# Lab10_Starter.net
KiCad netlist of a schematic drawn in EAGLE
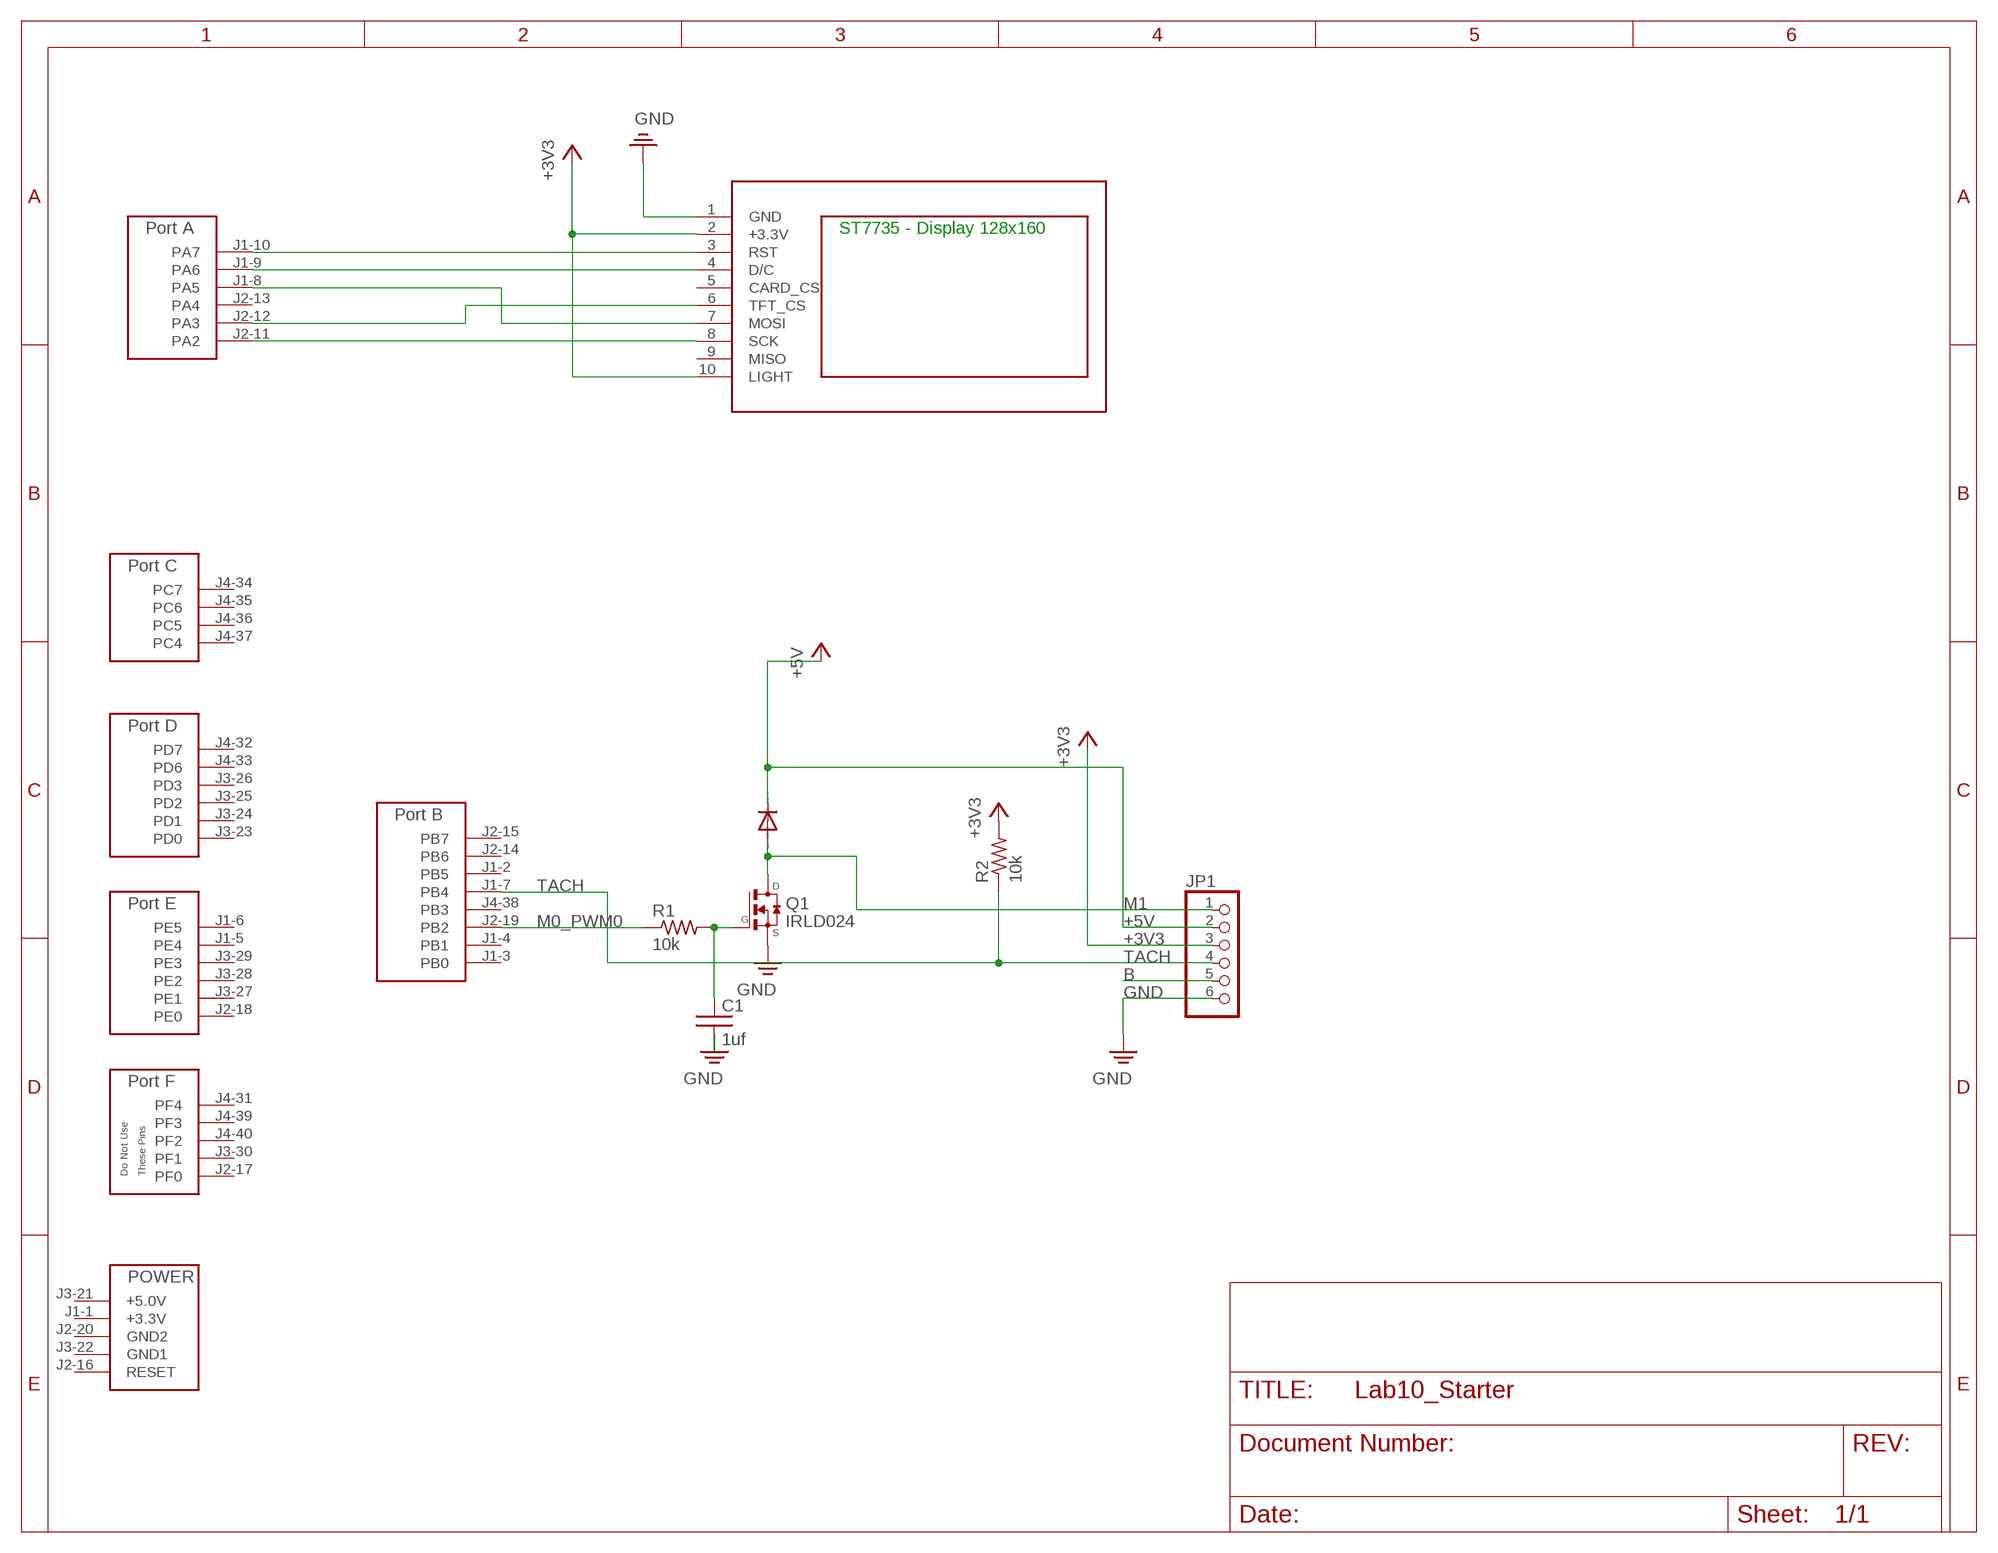
[diagram p0: schematic, sheet 1]

(export (version "E")
  (design (tool "Eeschema 10.0.6"))
  (components
    (comp (ref "C1")
      (value "1uf")
      (footprint "eagle-import:CAP200MIL")
      (libsource (lib "eagle-import") (part "CAPACITOR050-024X044"))
    )
    (comp (ref "D1")
      (value "1N914DO35-7")
      (footprint "eagle-import:DO35-7")
      (libsource (lib "eagle-import") (part "1N914DO35-7"))
    )
    (comp (ref "JP1")
      (value "PINHD-1X6")
      (footprint "eagle-import:1X06")
      (libsource (lib "eagle-import") (part "PINHD-1X6"))
    )
    (comp (ref "Q1")
      (value "IRLD024")
      (footprint "eagle-import:IRLD024")
      (libsource (lib "eagle-import") (part "IRLD024"))
    )
    (comp (ref "R1")
      (value "10k")
      (footprint "eagle-import:RES200MIL")
      (libsource (lib "eagle-import") (part "RESISTOR0204/5"))
    )
    (comp (ref "R2")
      (value "10k")
      (footprint "eagle-import:RES200MIL")
      (libsource (lib "eagle-import") (part "RESISTOR0204/5"))
    )
    (comp (ref "U$1")
      (value "TM4C_BP")
      (footprint "eagle-import:TM4C_BOOSTER_PACK")
      (libsource (lib "eagle-import") (part "TM4C_BP"))
    )
    (comp (ref "U$2")
      (value "ST7735")
      (footprint "eagle-import:ST7735")
      (libsource (lib "eagle-import") (part "ST7735"))
    )
    (comp (ref "U$3")
      (value "TM4C_BP")
      (footprint "eagle-import:TM4C_BOOSTER_PACK")
      (libsource (lib "eagle-import") (part "TM4C_BP"))
    )
  )
  (nets
    (net (code "1") (name "+3V3") (class "Default")
      (node (ref "JP1") (pin "3") (pinfunction "3_3") (pintype "passive"))
      (node (ref "R2") (pin "2") (pinfunction "2_2") (pintype "passive"))
      (node (ref "U$2") (pin "10") (pinfunction "LIGHT_10") (pintype "bidirectional"))
      (node (ref "U$2") (pin "2") (pinfunction "+3.3V_2") (pintype "bidirectional"))
    )
    (net (code "2") (name "+5V") (class "Default")
      (node (ref "D1") (pin "C") (pinfunction "C_C") (pintype "passive"))
      (node (ref "JP1") (pin "2") (pinfunction "2_2") (pintype "passive"))
    )
    (net (code "3") (name "/B") (class "Default")
      (node (ref "JP1") (pin "5") (pinfunction "5_5") (pintype "passive"))
    )
    (net (code "4") (name "/M0_PWM0") (class "Default")
      (node (ref "R1") (pin "1") (pinfunction "1_1") (pintype "passive"))
      (node (ref "U$1") (pin "J2-19") (pinfunction "PB2_J2-19") (pintype "bidirectional"))
    )
    (net (code "5") (name "/M1") (class "Default")
      (node (ref "D1") (pin "A") (pinfunction "A_A") (pintype "passive"))
      (node (ref "JP1") (pin "1") (pinfunction "1_1") (pintype "passive"))
      (node (ref "Q1") (pin "P$1") (pinfunction "D_P$1") (pintype "passive"))
    )
    (net (code "6") (name "/TACH") (class "Default")
      (node (ref "JP1") (pin "4") (pinfunction "4_4") (pintype "passive"))
      (node (ref "R2") (pin "1") (pinfunction "1_1") (pintype "passive"))
      (node (ref "U$1") (pin "J1-7") (pinfunction "PB4_J1-7") (pintype "bidirectional"))
    )
    (net (code "7") (name "GND") (class "Default")
      (node (ref "C1") (pin "2") (pinfunction "2_2") (pintype "passive"))
      (node (ref "JP1") (pin "6") (pinfunction "6_6") (pintype "passive"))
      (node (ref "Q1") (pin "P$4") (pinfunction "S_P$4") (pintype "passive"))
      (node (ref "U$2") (pin "1") (pinfunction "GND_1") (pintype "bidirectional"))
    )
    (net (code "8") (name "Net-(Q1-G)") (class "Default")
      (node (ref "C1") (pin "1") (pinfunction "1_1") (pintype "passive"))
      (node (ref "Q1") (pin "P$3") (pinfunction "G_P$3") (pintype "passive"))
      (node (ref "R1") (pin "2") (pinfunction "2_2") (pintype "passive"))
    )
    (net (code "9") (name "Net-(U$2-D{slash}C)") (class "Default")
      (node (ref "U$2") (pin "4") (pinfunction "D/C_4") (pintype "bidirectional"))
      (node (ref "U$3") (pin "J1-9") (pinfunction "PA6_J1-9") (pintype "bidirectional"))
    )
    (net (code "10") (name "Net-(U$2-MOSI)") (class "Default")
      (node (ref "U$2") (pin "7") (pinfunction "MOSI_7") (pintype "bidirectional"))
      (node (ref "U$3") (pin "J1-8") (pinfunction "PA5_J1-8") (pintype "bidirectional"))
    )
    (net (code "11") (name "Net-(U$2-RST)") (class "Default")
      (node (ref "U$2") (pin "3") (pinfunction "RST_3") (pintype "bidirectional"))
      (node (ref "U$3") (pin "J1-10") (pinfunction "PA7_J1-10") (pintype "bidirectional"))
    )
    (net (code "12") (name "Net-(U$2-SCK)") (class "Default")
      (node (ref "U$2") (pin "8") (pinfunction "SCK_8") (pintype "bidirectional"))
      (node (ref "U$3") (pin "J2-11") (pinfunction "PA2_J2-11") (pintype "bidirectional"))
    )
    (net (code "13") (name "Net-(U$2-TFT_CS)") (class "Default")
      (node (ref "U$2") (pin "6") (pinfunction "TFT_CS_6") (pintype "bidirectional"))
      (node (ref "U$3") (pin "J2-12") (pinfunction "PA3_J2-12") (pintype "bidirectional"))
    )
    (net (code "14") (name "unconnected-(U$1B-PB0-PadJ1-3)") (class "Default")
      (node (ref "U$1") (pin "J1-3") (pinfunction "PB0_J1-3") (pintype "bidirectional"))
    )
    (net (code "15") (name "unconnected-(U$1B-PB1-PadJ1-4)") (class "Default")
      (node (ref "U$1") (pin "J1-4") (pinfunction "PB1_J1-4") (pintype "bidirectional"))
    )
    (net (code "16") (name "unconnected-(U$1B-PB3-PadJ4-38)") (class "Default")
      (node (ref "U$1") (pin "J4-38") (pinfunction "PB3_J4-38") (pintype "bidirectional"))
    )
    (net (code "17") (name "unconnected-(U$1B-PB5-PadJ1-2)") (class "Default")
      (node (ref "U$1") (pin "J1-2") (pinfunction "PB5_J1-2") (pintype "bidirectional"))
    )
    (net (code "18") (name "unconnected-(U$1B-PB6-PadJ2-14)") (class "Default")
      (node (ref "U$1") (pin "J2-14") (pinfunction "PB6_J2-14") (pintype "bidirectional"))
    )
    (net (code "19") (name "unconnected-(U$1B-PB7-PadJ2-15)") (class "Default")
      (node (ref "U$1") (pin "J2-15") (pinfunction "PB7_J2-15") (pintype "bidirectional"))
    )
    (net (code "20") (name "unconnected-(U$1C-PC4-PadJ4-37)") (class "Default")
      (node (ref "U$1") (pin "J4-37") (pinfunction "PC4_J4-37") (pintype "bidirectional"))
    )
    (net (code "21") (name "unconnected-(U$1C-PC5-PadJ4-36)") (class "Default")
      (node (ref "U$1") (pin "J4-36") (pinfunction "PC5_J4-36") (pintype "bidirectional"))
    )
    (net (code "22") (name "unconnected-(U$1C-PC6-PadJ4-35)") (class "Default")
      (node (ref "U$1") (pin "J4-35") (pinfunction "PC6_J4-35") (pintype "bidirectional"))
    )
    (net (code "23") (name "unconnected-(U$1C-PC7-PadJ4-34)") (class "Default")
      (node (ref "U$1") (pin "J4-34") (pinfunction "PC7_J4-34") (pintype "bidirectional"))
    )
    (net (code "24") (name "unconnected-(U$1D-PD0-PadJ3-23)") (class "Default")
      (node (ref "U$1") (pin "J3-23") (pinfunction "PD0_J3-23") (pintype "bidirectional"))
    )
    (net (code "25") (name "unconnected-(U$1D-PD1-PadJ3-24)") (class "Default")
      (node (ref "U$1") (pin "J3-24") (pinfunction "PD1_J3-24") (pintype "bidirectional"))
    )
    (net (code "26") (name "unconnected-(U$1D-PD2-PadJ3-25)") (class "Default")
      (node (ref "U$1") (pin "J3-25") (pinfunction "PD2_J3-25") (pintype "bidirectional"))
    )
    (net (code "27") (name "unconnected-(U$1D-PD3-PadJ3-26)") (class "Default")
      (node (ref "U$1") (pin "J3-26") (pinfunction "PD3_J3-26") (pintype "bidirectional"))
    )
    (net (code "28") (name "unconnected-(U$1D-PD6-PadJ4-33)") (class "Default")
      (node (ref "U$1") (pin "J4-33") (pinfunction "PD6_J4-33") (pintype "bidirectional"))
    )
    (net (code "29") (name "unconnected-(U$1D-PD7-PadJ4-32)") (class "Default")
      (node (ref "U$1") (pin "J4-32") (pinfunction "PD7_J4-32") (pintype "bidirectional"))
    )
    (net (code "30") (name "unconnected-(U$1E-PE0-PadJ2-18)") (class "Default")
      (node (ref "U$1") (pin "J2-18") (pinfunction "PE0_J2-18") (pintype "bidirectional"))
    )
    (net (code "31") (name "unconnected-(U$1E-PE1-PadJ3-27)") (class "Default")
      (node (ref "U$1") (pin "J3-27") (pinfunction "PE1_J3-27") (pintype "bidirectional"))
    )
    (net (code "32") (name "unconnected-(U$1E-PE2-PadJ3-28)") (class "Default")
      (node (ref "U$1") (pin "J3-28") (pinfunction "PE2_J3-28") (pintype "bidirectional"))
    )
    (net (code "33") (name "unconnected-(U$1E-PE3-PadJ3-29)") (class "Default")
      (node (ref "U$1") (pin "J3-29") (pinfunction "PE3_J3-29") (pintype "bidirectional"))
    )
    (net (code "34") (name "unconnected-(U$1E-PE4-PadJ1-5)") (class "Default")
      (node (ref "U$1") (pin "J1-5") (pinfunction "PE4_J1-5") (pintype "bidirectional"))
    )
    (net (code "35") (name "unconnected-(U$1E-PE5-PadJ1-6)") (class "Default")
      (node (ref "U$1") (pin "J1-6") (pinfunction "PE5_J1-6") (pintype "bidirectional"))
    )
    (net (code "36") (name "unconnected-(U$1F-PF0-PadJ2-17)") (class "Default")
      (node (ref "U$1") (pin "J2-17") (pinfunction "PF0_J2-17") (pintype "bidirectional"))
    )
    (net (code "37") (name "unconnected-(U$1F-PF1-PadJ3-30)") (class "Default")
      (node (ref "U$1") (pin "J3-30") (pinfunction "PF1_J3-30") (pintype "bidirectional"))
    )
    (net (code "38") (name "unconnected-(U$1F-PF2-PadJ4-40)") (class "Default")
      (node (ref "U$1") (pin "J4-40") (pinfunction "PF2_J4-40") (pintype "bidirectional"))
    )
    (net (code "39") (name "unconnected-(U$1F-PF3-PadJ4-39)") (class "Default")
      (node (ref "U$1") (pin "J4-39") (pinfunction "PF3_J4-39") (pintype "bidirectional"))
    )
    (net (code "40") (name "unconnected-(U$1F-PF4-PadJ4-31)") (class "Default")
      (node (ref "U$1") (pin "J4-31") (pinfunction "PF4_J4-31") (pintype "bidirectional"))
    )
    (net (code "41") (name "unconnected-(U$1G-+3.3V-PadJ1-1)") (class "Default")
      (node (ref "U$1") (pin "J1-1") (pinfunction "+3.3V_J1-1") (pintype "bidirectional"))
    )
    (net (code "42") (name "unconnected-(U$1G-+5.0V-PadJ3-21)") (class "Default")
      (node (ref "U$1") (pin "J3-21") (pinfunction "+5.0V_J3-21") (pintype "bidirectional"))
    )
    (net (code "43") (name "unconnected-(U$1G-GND1-PadJ3-22)") (class "Default")
      (node (ref "U$1") (pin "J3-22") (pinfunction "GND1_J3-22") (pintype "bidirectional"))
    )
    (net (code "44") (name "unconnected-(U$1G-GND2-PadJ2-20)") (class "Default")
      (node (ref "U$1") (pin "J2-20") (pinfunction "GND2_J2-20") (pintype "bidirectional"))
    )
    (net (code "45") (name "unconnected-(U$1G-RESET-PadJ2-16)") (class "Default")
      (node (ref "U$1") (pin "J2-16") (pinfunction "RESET_J2-16") (pintype "bidirectional"))
    )
    (net (code "46") (name "unconnected-(U$2-CARD_CS-Pad5)") (class "Default")
      (node (ref "U$2") (pin "5") (pinfunction "CARD_CS_5") (pintype "bidirectional"))
    )
    (net (code "47") (name "unconnected-(U$2-MISO-Pad9)") (class "Default")
      (node (ref "U$2") (pin "9") (pinfunction "MISO_9") (pintype "bidirectional"))
    )
    (net (code "48") (name "unconnected-(U$3A-PA4-PadJ2-13)") (class "Default")
      (node (ref "U$3") (pin "J2-13") (pinfunction "PA4_J2-13") (pintype "bidirectional"))
    )
  )
)
